# POWER_FPGA.net
KiCad netlist of a schematic drawn in Altium Designer
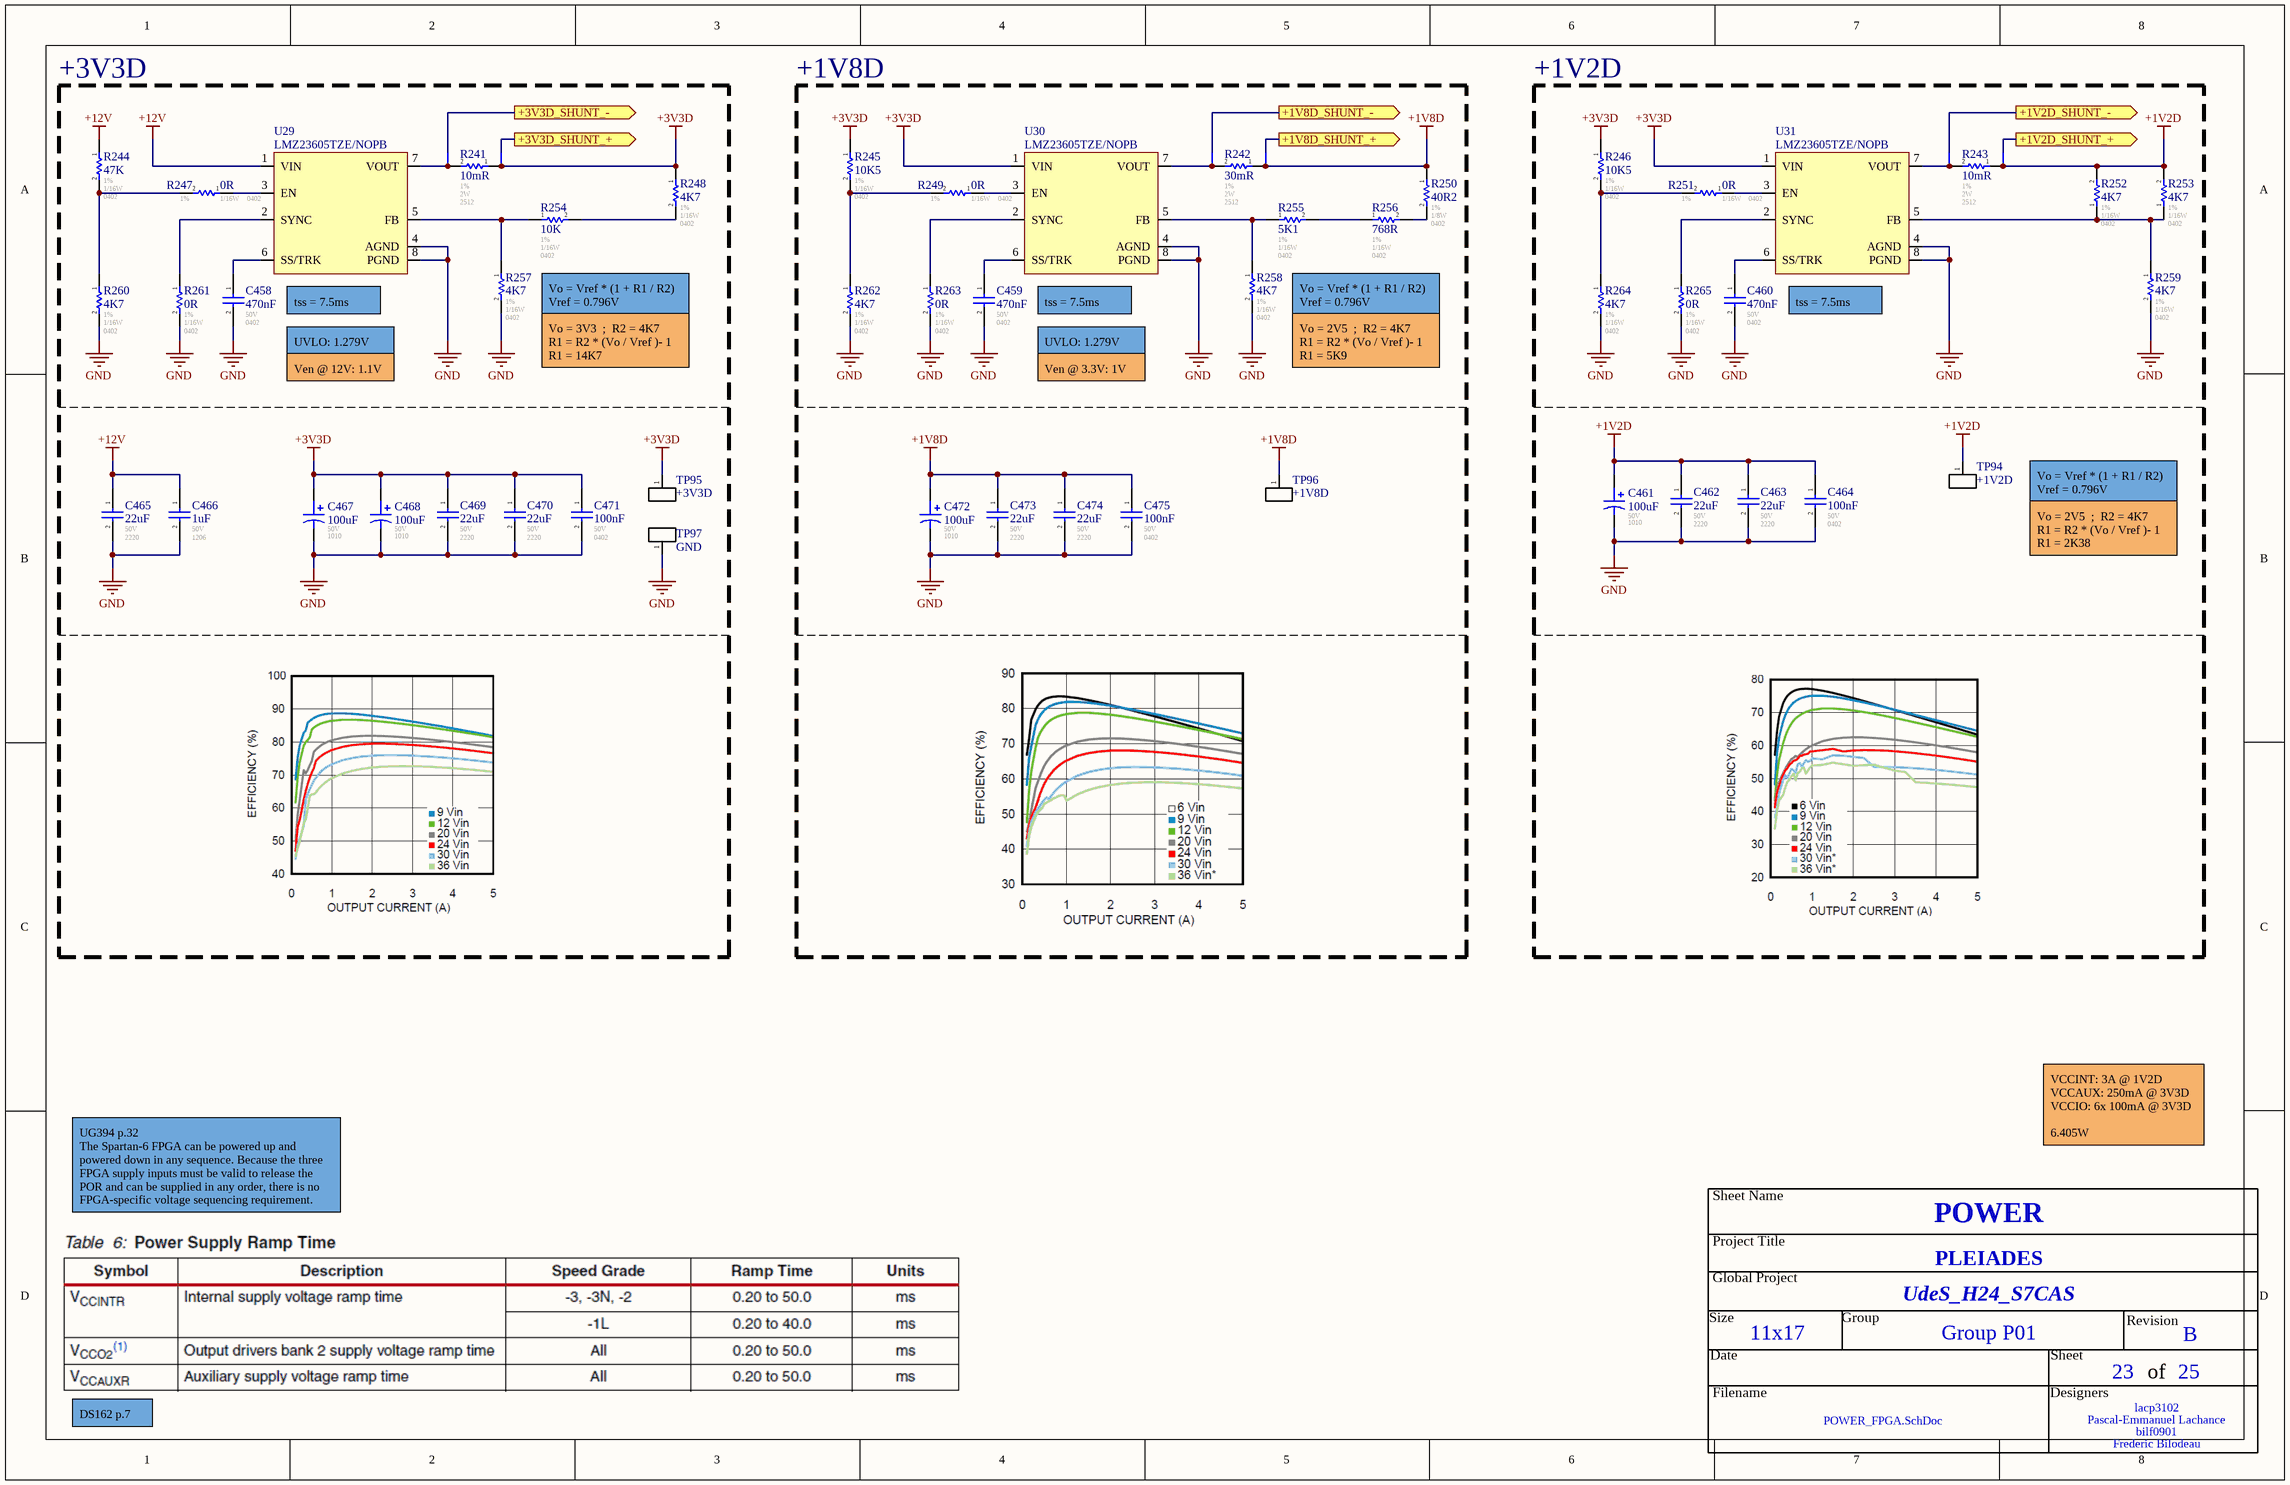
[diagram p0: POWER_FPGA.SchDoc]

(export (version "E")
  (design (tool "Eeschema 10.0.6"))
  (components
    (comp (ref "C458")
      (value "470nF")
      (footprint "0402")
      (description "CGA3E3X7R1H474K080AB\r\n0603 470nF 10% X7R Ceramic Capacitor")
      (fields
        (field (name "MFR") "TDK")
        (field (name "PART#") "CGA3E3X7R1H474K080AB")
        (field (name "VOLTAGE - RATED") "50V")
      )
      (libsource (lib "Symbols") (part "CAP_CER"))
    )
    (comp (ref "C459")
      (value "470nF")
      (footprint "0402")
      (description "CGA3E3X7R1H474K080AB\r\n0603 470nF 10% X7R Ceramic Capacitor")
      (fields
        (field (name "MFR") "TDK")
        (field (name "PART#") "CGA3E3X7R1H474K080AB")
        (field (name "VOLTAGE - RATED") "50V")
      )
      (libsource (lib "Symbols") (part "CAP_CER"))
    )
    (comp (ref "C460")
      (value "470nF")
      (footprint "0402")
      (description "CGA3E3X7R1H474K080AB\r\n0603 470nF 10% X7R Ceramic Capacitor")
      (fields
        (field (name "MFR") "TDK")
        (field (name "PART#") "CGA3E3X7R1H474K080AB")
        (field (name "VOLTAGE - RATED") "50V")
      )
      (libsource (lib "Symbols") (part "CAP_CER"))
    )
    (comp (ref "C461")
      (value "100uF")
      (footprint "CAP_ALU_1010_vishay")
      (description "CAP - ALU 100uF 20% 50V - 1010")
      (fields
        (field (name "MFG") "Vishay Dale")
        (field (name "MFG PART NUMBER") "MAL215099101E3")
        (field (name "VOLTAGE") "50V")
        (field (name "PACKAGE") "1010")
        (field (name "CREATEDBY") "Jonathan Bouchard")
      )
      (libsource (lib "S7CAS_LIB2023") (part "CAP_ALU_MAL215099101E3"))
    )
    (comp (ref "C462")
      (value "22uF")
      (footprint "2220")
      (description "CGA9P3X7R1H226M250KB\r\n2220 22uF 20% X7R Ceramic Capacitor")
      (fields
        (field (name "MFR") "TDK")
        (field (name "VOLTAGE - RATED") "50V")
        (field (name "TOLERANCE") "20%")
      )
      (libsource (lib "Symbols") (part "CAP_CER"))
    )
    (comp (ref "C463")
      (value "22uF")
      (footprint "2220")
      (description "CGA9P3X7R1H226M250KB\r\n2220 22uF 20% X7R Ceramic Capacitor")
      (fields
        (field (name "MFR") "TDK")
        (field (name "VOLTAGE - RATED") "50V")
        (field (name "TOLERANCE") "20%")
      )
      (libsource (lib "Symbols") (part "CAP_CER"))
    )
    (comp (ref "C464")
      (value "100nF")
      (footprint "0402")
      (description "GCM155R71H104KE02J\r\n0402 100nF 10% X7R Ceramic Capacitor")
      (fields
        (field (name "MFR") "Murata")
        (field (name "PART#") "GCM155R71H104KE02J")
        (field (name "VOLTAGE - RATED") "50V")
      )
      (libsource (lib "Symbols") (part "CAP_CER"))
    )
    (comp (ref "C465")
      (value "22uF")
      (footprint "2220")
      (description "CGA9P3X7R1H226M250KB\r\n2220 22uF 20% X7R Ceramic Capacitor")
      (fields
        (field (name "MFR") "TDK")
        (field (name "VOLTAGE - RATED") "50V")
        (field (name "TOLERANCE") "20%")
      )
      (libsource (lib "Symbols") (part "CAP_CER"))
    )
    (comp (ref "C466")
      (value "1uF")
      (footprint "1206")
      (description "GCJ31CR71H105KA12L\r\n1206 1uF 10% X7R Ceramic Capacitor")
      (fields
        (field (name "MFR") "Murata")
        (field (name "PART#") "GCJ31CR71H105KA12L")
        (field (name "VOLTAGE - RATED") "50V")
      )
      (libsource (lib "Symbols") (part "CAP_CER"))
    )
    (comp (ref "C467")
      (value "100uF")
      (footprint "CAP_ALU_1010_vishay")
      (description "CAP - ALU 100uF 20% 50V - 1010")
      (fields
        (field (name "MFG") "Vishay Dale")
        (field (name "MFG PART NUMBER") "MAL215099101E3")
        (field (name "VOLTAGE") "50V")
        (field (name "PACKAGE") "1010")
        (field (name "CREATEDBY") "Jonathan Bouchard")
      )
      (libsource (lib "S7CAS_LIB2023") (part "CAP_ALU_MAL215099101E3"))
    )
    (comp (ref "C468")
      (value "100uF")
      (footprint "CAP_ALU_1010_vishay")
      (description "CAP - ALU 100uF 20% 50V - 1010")
      (fields
        (field (name "MFG") "Vishay Dale")
        (field (name "MFG PART NUMBER") "MAL215099101E3")
        (field (name "VOLTAGE") "50V")
        (field (name "PACKAGE") "1010")
        (field (name "CREATEDBY") "Jonathan Bouchard")
      )
      (libsource (lib "S7CAS_LIB2023") (part "CAP_ALU_MAL215099101E3"))
    )
    (comp (ref "C469")
      (value "22uF")
      (footprint "2220")
      (description "CGA9P3X7R1H226M250KB\r\n2220 22uF 20% X7R Ceramic Capacitor")
      (fields
        (field (name "MFR") "TDK")
        (field (name "VOLTAGE - RATED") "50V")
        (field (name "TOLERANCE") "20%")
      )
      (libsource (lib "Symbols") (part "CAP_CER"))
    )
    (comp (ref "C470")
      (value "22uF")
      (footprint "2220")
      (description "CGA9P3X7R1H226M250KB\r\n2220 22uF 20% X7R Ceramic Capacitor")
      (fields
        (field (name "MFR") "TDK")
        (field (name "VOLTAGE - RATED") "50V")
        (field (name "TOLERANCE") "20%")
      )
      (libsource (lib "Symbols") (part "CAP_CER"))
    )
    (comp (ref "C471")
      (value "100nF")
      (footprint "0402")
      (description "GCM155R71H104KE02J\r\n0402 100nF 10% X7R Ceramic Capacitor")
      (fields
        (field (name "MFR") "Murata")
        (field (name "PART#") "GCM155R71H104KE02J")
        (field (name "VOLTAGE - RATED") "50V")
      )
      (libsource (lib "Symbols") (part "CAP_CER"))
    )
    (comp (ref "C472")
      (value "100uF")
      (footprint "CAP_ALU_1010_vishay")
      (description "CAP - ALU 100uF 20% 50V - 1010")
      (fields
        (field (name "MFG") "Vishay Dale")
        (field (name "MFG PART NUMBER") "MAL215099101E3")
        (field (name "VOLTAGE") "50V")
        (field (name "PACKAGE") "1010")
        (field (name "CREATEDBY") "Jonathan Bouchard")
      )
      (libsource (lib "S7CAS_LIB2023") (part "CAP_ALU_MAL215099101E3"))
    )
    (comp (ref "C473")
      (value "22uF")
      (footprint "2220")
      (description "CGA9P3X7R1H226M250KB\r\n2220 22uF 20% X7R Ceramic Capacitor")
      (fields
        (field (name "MFR") "TDK")
        (field (name "VOLTAGE - RATED") "50V")
        (field (name "TOLERANCE") "20%")
      )
      (libsource (lib "Symbols") (part "CAP_CER"))
    )
    (comp (ref "C474")
      (value "22uF")
      (footprint "2220")
      (description "CGA9P3X7R1H226M250KB\r\n2220 22uF 20% X7R Ceramic Capacitor")
      (fields
        (field (name "MFR") "TDK")
        (field (name "VOLTAGE - RATED") "50V")
        (field (name "TOLERANCE") "20%")
      )
      (libsource (lib "Symbols") (part "CAP_CER"))
    )
    (comp (ref "C475")
      (value "100nF")
      (footprint "0402")
      (description "GCM155R71H104KE02J\r\n0402 100nF 10% X7R Ceramic Capacitor")
      (fields
        (field (name "MFR") "Murata")
        (field (name "PART#") "GCM155R71H104KE02J")
        (field (name "VOLTAGE - RATED") "50V")
      )
      (libsource (lib "Symbols") (part "CAP_CER"))
    )
    (comp (ref "NT46")
      (value "Net Tie")
      (footprint "NETTIE_5")
      (libsource (lib "Symbols") (part "NET_TIE_SMALL"))
    )
    (comp (ref "NT47")
      (value "Net Tie")
      (footprint "NETTIE_5")
      (libsource (lib "Symbols") (part "NET_TIE_SMALL"))
    )
    (comp (ref "NT48")
      (value "Net Tie")
      (footprint "NETTIE_5")
      (libsource (lib "Symbols") (part "NET_TIE_SMALL"))
    )
    (comp (ref "NT49")
      (value "Net Tie")
      (footprint "NETTIE_5")
      (libsource (lib "Symbols") (part "NET_TIE_SMALL"))
    )
    (comp (ref "NT50")
      (value "Net Tie")
      (footprint "NETTIE_5")
      (libsource (lib "Symbols") (part "NET_TIE_SMALL"))
    )
    (comp (ref "NT51")
      (value "Net Tie")
      (footprint "NETTIE_5")
      (libsource (lib "Symbols") (part "NET_TIE_SMALL"))
    )
    (comp (ref "R241")
      (value "10mR")
      (footprint "RES_2512")
      (description "CSRN2512FK10L0")
      (fields
        (field (name "TOLERANCE") "1%")
        (field (name "POWER") "2W")
        (field (name "PACKAGE / CASE") "2512")
      )
      (libsource (lib "Symbols") (part "RESISTOR"))
    )
    (comp (ref "R242")
      (value "30mR")
      (footprint "RES_2512")
      (description "CSRN2512FK30L0")
      (fields
        (field (name "TOLERANCE") "1%")
        (field (name "POWER") "2W")
        (field (name "PACKAGE / CASE") "2512")
      )
      (libsource (lib "Symbols") (part "RESISTOR"))
    )
    (comp (ref "R243")
      (value "10mR")
      (footprint "RES_2512")
      (description "CSRN2512FK10L0")
      (fields
        (field (name "TOLERANCE") "1%")
        (field (name "POWER") "2W")
        (field (name "PACKAGE / CASE") "2512")
      )
      (libsource (lib "Symbols") (part "RESISTOR"))
    )
    (comp (ref "R244")
      (value "47K")
      (footprint "RES_0402")
      (fields
        (field (name "TOLERANCE") "1%")
        (field (name "POWER") "1/16W")
        (field (name "PACKAGE / CASE") "0402")
      )
      (libsource (lib "Symbols") (part "RESISTOR"))
    )
    (comp (ref "R245")
      (value "10K5")
      (footprint "RES_0402")
      (fields
        (field (name "TOLERANCE") "1%")
        (field (name "POWER") "1/16W")
        (field (name "PACKAGE / CASE") "0402")
      )
      (libsource (lib "Symbols") (part "RESISTOR"))
    )
    (comp (ref "R246")
      (value "10K5")
      (footprint "RES_0402")
      (fields
        (field (name "TOLERANCE") "1%")
        (field (name "POWER") "1/16W")
        (field (name "PACKAGE / CASE") "0402")
      )
      (libsource (lib "Symbols") (part "RESISTOR"))
    )
    (comp (ref "R247")
      (value "0R")
      (footprint "RES_0402")
      (fields
        (field (name "TOLERANCE") "1%")
        (field (name "POWER") "1/16W")
        (field (name "PACKAGE / CASE") "0402")
      )
      (libsource (lib "Symbols") (part "RESISTOR"))
    )
    (comp (ref "R248")
      (value "4K7")
      (footprint "RES_0402")
      (fields
        (field (name "TOLERANCE") "1%")
        (field (name "POWER") "1/16W")
        (field (name "PACKAGE / CASE") "0402")
      )
      (libsource (lib "Symbols") (part "RESISTOR"))
    )
    (comp (ref "R249")
      (value "0R")
      (footprint "RES_0402")
      (fields
        (field (name "TOLERANCE") "1%")
        (field (name "POWER") "1/16W")
        (field (name "PACKAGE / CASE") "0402")
      )
      (libsource (lib "Symbols") (part "RESISTOR"))
    )
    (comp (ref "R250")
      (value "40R2")
      (footprint "RES_0402")
      (fields
        (field (name "TOLERANCE") "1%")
        (field (name "POWER") "1/8W")
        (field (name "PACKAGE / CASE") "0402")
      )
      (libsource (lib "Symbols") (part "RESISTOR"))
    )
    (comp (ref "R251")
      (value "0R")
      (footprint "RES_0402")
      (fields
        (field (name "TOLERANCE") "1%")
        (field (name "POWER") "1/16W")
        (field (name "PACKAGE / CASE") "0402")
      )
      (libsource (lib "Symbols") (part "RESISTOR"))
    )
    (comp (ref "R252")
      (value "4K7")
      (footprint "RES_0402")
      (fields
        (field (name "TOLERANCE") "1%")
        (field (name "POWER") "1/16W")
        (field (name "PACKAGE / CASE") "0402")
      )
      (libsource (lib "Symbols") (part "RESISTOR"))
    )
    (comp (ref "R253")
      (value "4K7")
      (footprint "RES_0402")
      (fields
        (field (name "TOLERANCE") "1%")
        (field (name "POWER") "1/16W")
        (field (name "PACKAGE / CASE") "0402")
      )
      (libsource (lib "Symbols") (part "RESISTOR"))
    )
    (comp (ref "R254")
      (value "10K")
      (footprint "RES_0402")
      (fields
        (field (name "TOLERANCE") "1%")
        (field (name "POWER") "1/16W")
        (field (name "PACKAGE / CASE") "0402")
      )
      (libsource (lib "Symbols") (part "RESISTOR"))
    )
    (comp (ref "R255")
      (value "5K1")
      (footprint "RES_0402")
      (fields
        (field (name "TOLERANCE") "1%")
        (field (name "POWER") "1/16W")
        (field (name "PACKAGE / CASE") "0402")
      )
      (libsource (lib "Symbols") (part "RESISTOR"))
    )
    (comp (ref "R256")
      (value "768R")
      (footprint "RES_0402")
      (fields
        (field (name "TOLERANCE") "1%")
        (field (name "POWER") "1/16W")
        (field (name "PACKAGE / CASE") "0402")
      )
      (libsource (lib "Symbols") (part "RESISTOR"))
    )
    (comp (ref "R257")
      (value "4K7")
      (footprint "RES_0402")
      (fields
        (field (name "TOLERANCE") "1%")
        (field (name "POWER") "1/16W")
        (field (name "PACKAGE / CASE") "0402")
      )
      (libsource (lib "Symbols") (part "RESISTOR"))
    )
    (comp (ref "R258")
      (value "4K7")
      (footprint "RES_0402")
      (fields
        (field (name "TOLERANCE") "1%")
        (field (name "POWER") "1/16W")
        (field (name "PACKAGE / CASE") "0402")
      )
      (libsource (lib "Symbols") (part "RESISTOR"))
    )
    (comp (ref "R259")
      (value "4K7")
      (footprint "RES_0402")
      (fields
        (field (name "TOLERANCE") "1%")
        (field (name "POWER") "1/16W")
        (field (name "PACKAGE / CASE") "0402")
      )
      (libsource (lib "Symbols") (part "RESISTOR"))
    )
    (comp (ref "R260")
      (value "4K7")
      (footprint "RES_0402")
      (fields
        (field (name "TOLERANCE") "1%")
        (field (name "POWER") "1/16W")
        (field (name "PACKAGE / CASE") "0402")
      )
      (libsource (lib "Symbols") (part "RESISTOR"))
    )
    (comp (ref "R261")
      (value "0R")
      (footprint "RES_0402")
      (fields
        (field (name "TOLERANCE") "1%")
        (field (name "POWER") "1/16W")
        (field (name "PACKAGE / CASE") "0402")
      )
      (libsource (lib "Symbols") (part "RESISTOR"))
    )
    (comp (ref "R262")
      (value "4K7")
      (footprint "RES_0402")
      (fields
        (field (name "TOLERANCE") "1%")
        (field (name "POWER") "1/16W")
        (field (name "PACKAGE / CASE") "0402")
      )
      (libsource (lib "Symbols") (part "RESISTOR"))
    )
    (comp (ref "R263")
      (value "0R")
      (footprint "RES_0402")
      (fields
        (field (name "TOLERANCE") "1%")
        (field (name "POWER") "1/16W")
        (field (name "PACKAGE / CASE") "0402")
      )
      (libsource (lib "Symbols") (part "RESISTOR"))
    )
    (comp (ref "R264")
      (value "4K7")
      (footprint "RES_0402")
      (fields
        (field (name "TOLERANCE") "1%")
        (field (name "POWER") "1/16W")
        (field (name "PACKAGE / CASE") "0402")
      )
      (libsource (lib "Symbols") (part "RESISTOR"))
    )
    (comp (ref "R265")
      (value "0R")
      (footprint "RES_0402")
      (fields
        (field (name "TOLERANCE") "1%")
        (field (name "POWER") "1/16W")
        (field (name "PACKAGE / CASE") "0402")
      )
      (libsource (lib "Symbols") (part "RESISTOR"))
    )
    (comp (ref "TP94")
      (value "+1V2D")
      (footprint "TP_HOLE")
      (description "Test Point")
      (libsource (lib "Symbols") (part "TESTPOINT"))
    )
    (comp (ref "TP95")
      (value "+3V3D")
      (footprint "TP_HOLE")
      (description "Test Point")
      (libsource (lib "Symbols") (part "TESTPOINT"))
    )
    (comp (ref "TP96")
      (value "+1V8D")
      (footprint "TP_HOLE")
      (description "Test Point")
      (libsource (lib "Symbols") (part "TESTPOINT"))
    )
    (comp (ref "TP97")
      (value "GND")
      (footprint "TP_HOLE")
      (description "Test Point")
      (libsource (lib "Symbols") (part "TESTPOINT"))
    )
    (comp (ref "U29")
      (value "LMZ23605TZE/NOPB")
      (footprint "REG_SWR_LMZ23605TZE/NOPB")
      (description "REG - IC BUCK SYNC 36V 5A - TO-PMOD-7")
      (fields
        (field (name "CREATEDBY/DATE") "Arnaud Samson - 05/07/18")
        (field (name "VERIFIEDBY") "Jonathan Bouchard 2018-07-13")
      )
      (libsource (lib "S7CAS_LIB2023") (part "REG_SWR_LMZ23605TZE/NOPB"))
    )
    (comp (ref "U30")
      (value "LMZ23605TZE/NOPB")
      (footprint "REG_SWR_LMZ23605TZE/NOPB")
      (description "REG - IC BUCK SYNC 36V 5A - TO-PMOD-7")
      (fields
        (field (name "CREATEDBY/DATE") "Arnaud Samson - 05/07/18")
        (field (name "VERIFIEDBY") "Jonathan Bouchard 2018-07-13")
      )
      (libsource (lib "S7CAS_LIB2023") (part "REG_SWR_LMZ23605TZE/NOPB"))
    )
    (comp (ref "U31")
      (value "LMZ23605TZE/NOPB")
      (footprint "REG_SWR_LMZ23605TZE/NOPB")
      (description "REG - IC BUCK SYNC 36V 5A - TO-PMOD-7")
      (fields
        (field (name "CREATEDBY/DATE") "Arnaud Samson - 05/07/18")
        (field (name "VERIFIEDBY") "Jonathan Bouchard 2018-07-13")
      )
      (libsource (lib "S7CAS_LIB2023") (part "REG_SWR_LMZ23605TZE/NOPB"))
    )
  )
  (nets
    (net (code "1") (name "+1V2D") (class "Default")
      (node (ref "C461") (pin "1") (pinfunction "1_1") (pintype "passive"))
      (node (ref "C462") (pin "1") (pinfunction "1_1") (pintype "passive"))
      (node (ref "C463") (pin "1") (pinfunction "1_1") (pintype "passive"))
      (node (ref "C464") (pin "1") (pinfunction "1_1") (pintype "passive"))
      (node (ref "NT51") (pin "1") (pinfunction "1_1") (pintype "passive"))
      (node (ref "R243") (pin "1") (pinfunction "1_1") (pintype "passive"))
      (node (ref "R252") (pin "2") (pinfunction "2_2") (pintype "passive"))
      (node (ref "R253") (pin "2") (pinfunction "2_2") (pintype "passive"))
      (node (ref "TP94") (pin "1") (pinfunction "A_1") (pintype "passive"))
    )
    (net (code "2") (name "+1V8D") (class "Default")
      (node (ref "C472") (pin "1") (pinfunction "1_1") (pintype "passive"))
      (node (ref "C473") (pin "1") (pinfunction "1_1") (pintype "passive"))
      (node (ref "C474") (pin "1") (pinfunction "1_1") (pintype "passive"))
      (node (ref "C475") (pin "1") (pinfunction "1_1") (pintype "passive"))
      (node (ref "NT49") (pin "1") (pinfunction "1_1") (pintype "passive"))
      (node (ref "R242") (pin "1") (pinfunction "1_1") (pintype "passive"))
      (node (ref "R250") (pin "1") (pinfunction "1_1") (pintype "passive"))
      (node (ref "TP96") (pin "1") (pinfunction "A_1") (pintype "passive"))
    )
    (net (code "3") (name "+3V3D") (class "Default")
      (node (ref "C467") (pin "1") (pinfunction "1_1") (pintype "passive"))
      (node (ref "C468") (pin "1") (pinfunction "1_1") (pintype "passive"))
      (node (ref "C469") (pin "1") (pinfunction "1_1") (pintype "passive"))
      (node (ref "C470") (pin "1") (pinfunction "1_1") (pintype "passive"))
      (node (ref "C471") (pin "1") (pinfunction "1_1") (pintype "passive"))
      (node (ref "NT47") (pin "1") (pinfunction "1_1") (pintype "passive"))
      (node (ref "R241") (pin "1") (pinfunction "1_1") (pintype "passive"))
      (node (ref "R245") (pin "1") (pinfunction "1_1") (pintype "passive"))
      (node (ref "R246") (pin "1") (pinfunction "1_1") (pintype "passive"))
      (node (ref "R248") (pin "1") (pinfunction "1_1") (pintype "passive"))
      (node (ref "TP95") (pin "1") (pinfunction "A_1") (pintype "passive"))
      (node (ref "U30") (pin "1") (pinfunction "VIN_1") (pintype "passive"))
      (node (ref "U31") (pin "1") (pinfunction "VIN_1") (pintype "passive"))
    )
    (net (code "4") (name "+12V") (class "Default")
      (node (ref "C465") (pin "1") (pinfunction "1_1") (pintype "passive"))
      (node (ref "C466") (pin "1") (pinfunction "1_1") (pintype "passive"))
      (node (ref "R244") (pin "1") (pinfunction "1_1") (pintype "passive"))
      (node (ref "U29") (pin "1") (pinfunction "VIN_1") (pintype "passive"))
    )
    (net (code "5") (name "/+1V2D_SHUNT_+") (class "Default")
      (node (ref "NT51") (pin "2") (pinfunction "2_2") (pintype "passive"))
    )
    (net (code "6") (name "/+1V2D_SHUNT_-") (class "Default")
      (node (ref "NT50") (pin "2") (pinfunction "2_2") (pintype "passive"))
    )
    (net (code "7") (name "/+1V8D_SHUNT_+") (class "Default")
      (node (ref "NT49") (pin "2") (pinfunction "2_2") (pintype "passive"))
    )
    (net (code "8") (name "/+1V8D_SHUNT_-") (class "Default")
      (node (ref "NT48") (pin "2") (pinfunction "2_2") (pintype "passive"))
    )
    (net (code "9") (name "/+3V3D_SHUNT_+") (class "Default")
      (node (ref "NT47") (pin "2") (pinfunction "2_2") (pintype "passive"))
    )
    (net (code "10") (name "/+3V3D_SHUNT_-") (class "Default")
      (node (ref "NT46") (pin "2") (pinfunction "2_2") (pintype "passive"))
    )
    (net (code "11") (name "GND") (class "Default")
      (node (ref "C458") (pin "2") (pinfunction "2_2") (pintype "passive"))
      (node (ref "C459") (pin "2") (pinfunction "2_2") (pintype "passive"))
      (node (ref "C460") (pin "2") (pinfunction "2_2") (pintype "passive"))
      (node (ref "C461") (pin "2") (pinfunction "2_2") (pintype "passive"))
      (node (ref "C462") (pin "2") (pinfunction "2_2") (pintype "passive"))
      (node (ref "C463") (pin "2") (pinfunction "2_2") (pintype "passive"))
      (node (ref "C464") (pin "2") (pinfunction "2_2") (pintype "passive"))
      (node (ref "C465") (pin "2") (pinfunction "2_2") (pintype "passive"))
      (node (ref "C466") (pin "2") (pinfunction "2_2") (pintype "passive"))
      (node (ref "C467") (pin "2") (pinfunction "2_2") (pintype "passive"))
      (node (ref "C468") (pin "2") (pinfunction "2_2") (pintype "passive"))
      (node (ref "C469") (pin "2") (pinfunction "2_2") (pintype "passive"))
      (node (ref "C470") (pin "2") (pinfunction "2_2") (pintype "passive"))
      (node (ref "C471") (pin "2") (pinfunction "2_2") (pintype "passive"))
      (node (ref "C472") (pin "2") (pinfunction "2_2") (pintype "passive"))
      (node (ref "C473") (pin "2") (pinfunction "2_2") (pintype "passive"))
      (node (ref "C474") (pin "2") (pinfunction "2_2") (pintype "passive"))
      (node (ref "C475") (pin "2") (pinfunction "2_2") (pintype "passive"))
      (node (ref "R257") (pin "2") (pinfunction "2_2") (pintype "passive"))
      (node (ref "R258") (pin "2") (pinfunction "2_2") (pintype "passive"))
      (node (ref "R259") (pin "2") (pinfunction "2_2") (pintype "passive"))
      (node (ref "R260") (pin "2") (pinfunction "2_2") (pintype "passive"))
      (node (ref "R261") (pin "2") (pinfunction "2_2") (pintype "passive"))
      (node (ref "R262") (pin "2") (pinfunction "2_2") (pintype "passive"))
      (node (ref "R263") (pin "2") (pinfunction "2_2") (pintype "passive"))
      (node (ref "R264") (pin "2") (pinfunction "2_2") (pintype "passive"))
      (node (ref "R265") (pin "2") (pinfunction "2_2") (pintype "passive"))
      (node (ref "TP97") (pin "1") (pinfunction "A_1") (pintype "passive"))
      (node (ref "U29") (pin "4") (pinfunction "AGND_4") (pintype "passive"))
      (node (ref "U29") (pin "8") (pinfunction "PGND_8") (pintype "passive"))
      (node (ref "U30") (pin "4") (pinfunction "AGND_4") (pintype "passive"))
      (node (ref "U30") (pin "8") (pinfunction "PGND_8") (pintype "passive"))
      (node (ref "U31") (pin "4") (pinfunction "AGND_4") (pintype "passive"))
      (node (ref "U31") (pin "8") (pinfunction "PGND_8") (pintype "passive"))
    )
    (net (code "12") (name "Net-(R244-Pad2)") (class "Default")
      (node (ref "R244") (pin "2") (pinfunction "2_2") (pintype "passive"))
      (node (ref "R247") (pin "2") (pinfunction "2_2") (pintype "passive"))
      (node (ref "R260") (pin "1") (pinfunction "1_1") (pintype "passive"))
    )
    (net (code "13") (name "Net-(R245-Pad2)") (class "Default")
      (node (ref "R245") (pin "2") (pinfunction "2_2") (pintype "passive"))
      (node (ref "R249") (pin "2") (pinfunction "2_2") (pintype "passive"))
      (node (ref "R262") (pin "1") (pinfunction "1_1") (pintype "passive"))
    )
    (net (code "14") (name "Net-(R246-Pad2)") (class "Default")
      (node (ref "R246") (pin "2") (pinfunction "2_2") (pintype "passive"))
      (node (ref "R251") (pin "2") (pinfunction "2_2") (pintype "passive"))
      (node (ref "R264") (pin "1") (pinfunction "1_1") (pintype "passive"))
    )
    (net (code "15") (name "Net-(R248-Pad2)") (class "Default")
      (node (ref "R248") (pin "2") (pinfunction "2_2") (pintype "passive"))
      (node (ref "R254") (pin "2") (pinfunction "2_2") (pintype "passive"))
    )
    (net (code "16") (name "Net-(R250-Pad2)") (class "Default")
      (node (ref "R250") (pin "2") (pinfunction "2_2") (pintype "passive"))
      (node (ref "R256") (pin "2") (pinfunction "2_2") (pintype "passive"))
    )
    (net (code "17") (name "Net-(R255-Pad2)") (class "Default")
      (node (ref "R255") (pin "2") (pinfunction "2_2") (pintype "passive"))
      (node (ref "R256") (pin "1") (pinfunction "1_1") (pintype "passive"))
    )
    (net (code "18") (name "Net-(U29-EN)") (class "Default")
      (node (ref "R247") (pin "1") (pinfunction "1_1") (pintype "passive"))
      (node (ref "U29") (pin "3") (pinfunction "EN_3") (pintype "passive"))
    )
    (net (code "19") (name "Net-(U29-FB)") (class "Default")
      (node (ref "R254") (pin "1") (pinfunction "1_1") (pintype "passive"))
      (node (ref "R257") (pin "1") (pinfunction "1_1") (pintype "passive"))
      (node (ref "U29") (pin "5") (pinfunction "FB_5") (pintype "passive"))
    )
    (net (code "20") (name "Net-(U29-SS{slash}TRK)") (class "Default")
      (node (ref "C458") (pin "1") (pinfunction "1_1") (pintype "passive"))
      (node (ref "U29") (pin "6") (pinfunction "SS/TRK_6") (pintype "passive"))
    )
    (net (code "21") (name "Net-(U29-SYNC)") (class "Default")
      (node (ref "R261") (pin "1") (pinfunction "1_1") (pintype "passive"))
      (node (ref "U29") (pin "2") (pinfunction "SYNC_2") (pintype "passive"))
    )
    (net (code "22") (name "Net-(U29-VOUT)") (class "Default")
      (node (ref "NT46") (pin "1") (pinfunction "1_1") (pintype "passive"))
      (node (ref "R241") (pin "2") (pinfunction "2_2") (pintype "passive"))
      (node (ref "U29") (pin "7") (pinfunction "VOUT_7") (pintype "passive"))
    )
    (net (code "23") (name "Net-(U30-EN)") (class "Default")
      (node (ref "R249") (pin "1") (pinfunction "1_1") (pintype "passive"))
      (node (ref "U30") (pin "3") (pinfunction "EN_3") (pintype "passive"))
    )
    (net (code "24") (name "Net-(U30-FB)") (class "Default")
      (node (ref "R255") (pin "1") (pinfunction "1_1") (pintype "passive"))
      (node (ref "R258") (pin "1") (pinfunction "1_1") (pintype "passive"))
      (node (ref "U30") (pin "5") (pinfunction "FB_5") (pintype "passive"))
    )
    (net (code "25") (name "Net-(U30-SS{slash}TRK)") (class "Default")
      (node (ref "C459") (pin "1") (pinfunction "1_1") (pintype "passive"))
      (node (ref "U30") (pin "6") (pinfunction "SS/TRK_6") (pintype "passive"))
    )
    (net (code "26") (name "Net-(U30-SYNC)") (class "Default")
      (node (ref "R263") (pin "1") (pinfunction "1_1") (pintype "passive"))
      (node (ref "U30") (pin "2") (pinfunction "SYNC_2") (pintype "passive"))
    )
    (net (code "27") (name "Net-(U30-VOUT)") (class "Default")
      (node (ref "NT48") (pin "1") (pinfunction "1_1") (pintype "passive"))
      (node (ref "R242") (pin "2") (pinfunction "2_2") (pintype "passive"))
      (node (ref "U30") (pin "7") (pinfunction "VOUT_7") (pintype "passive"))
    )
    (net (code "28") (name "Net-(U31-EN)") (class "Default")
      (node (ref "R251") (pin "1") (pinfunction "1_1") (pintype "passive"))
      (node (ref "U31") (pin "3") (pinfunction "EN_3") (pintype "passive"))
    )
    (net (code "29") (name "Net-(U31-FB)") (class "Default")
      (node (ref "R252") (pin "1") (pinfunction "1_1") (pintype "passive"))
      (node (ref "R253") (pin "1") (pinfunction "1_1") (pintype "passive"))
      (node (ref "R259") (pin "1") (pinfunction "1_1") (pintype "passive"))
      (node (ref "U31") (pin "5") (pinfunction "FB_5") (pintype "passive"))
    )
    (net (code "30") (name "Net-(U31-SS{slash}TRK)") (class "Default")
      (node (ref "C460") (pin "1") (pinfunction "1_1") (pintype "passive"))
      (node (ref "U31") (pin "6") (pinfunction "SS/TRK_6") (pintype "passive"))
    )
    (net (code "31") (name "Net-(U31-SYNC)") (class "Default")
      (node (ref "R265") (pin "1") (pinfunction "1_1") (pintype "passive"))
      (node (ref "U31") (pin "2") (pinfunction "SYNC_2") (pintype "passive"))
    )
    (net (code "32") (name "Net-(U31-VOUT)") (class "Default")
      (node (ref "NT50") (pin "1") (pinfunction "1_1") (pintype "passive"))
      (node (ref "R243") (pin "2") (pinfunction "2_2") (pintype "passive"))
      (node (ref "U31") (pin "7") (pinfunction "VOUT_7") (pintype "passive"))
    )
  )
)
